# STM32-G0-Dip-Module.net
KiCad netlist of a schematic drawn in EAGLE
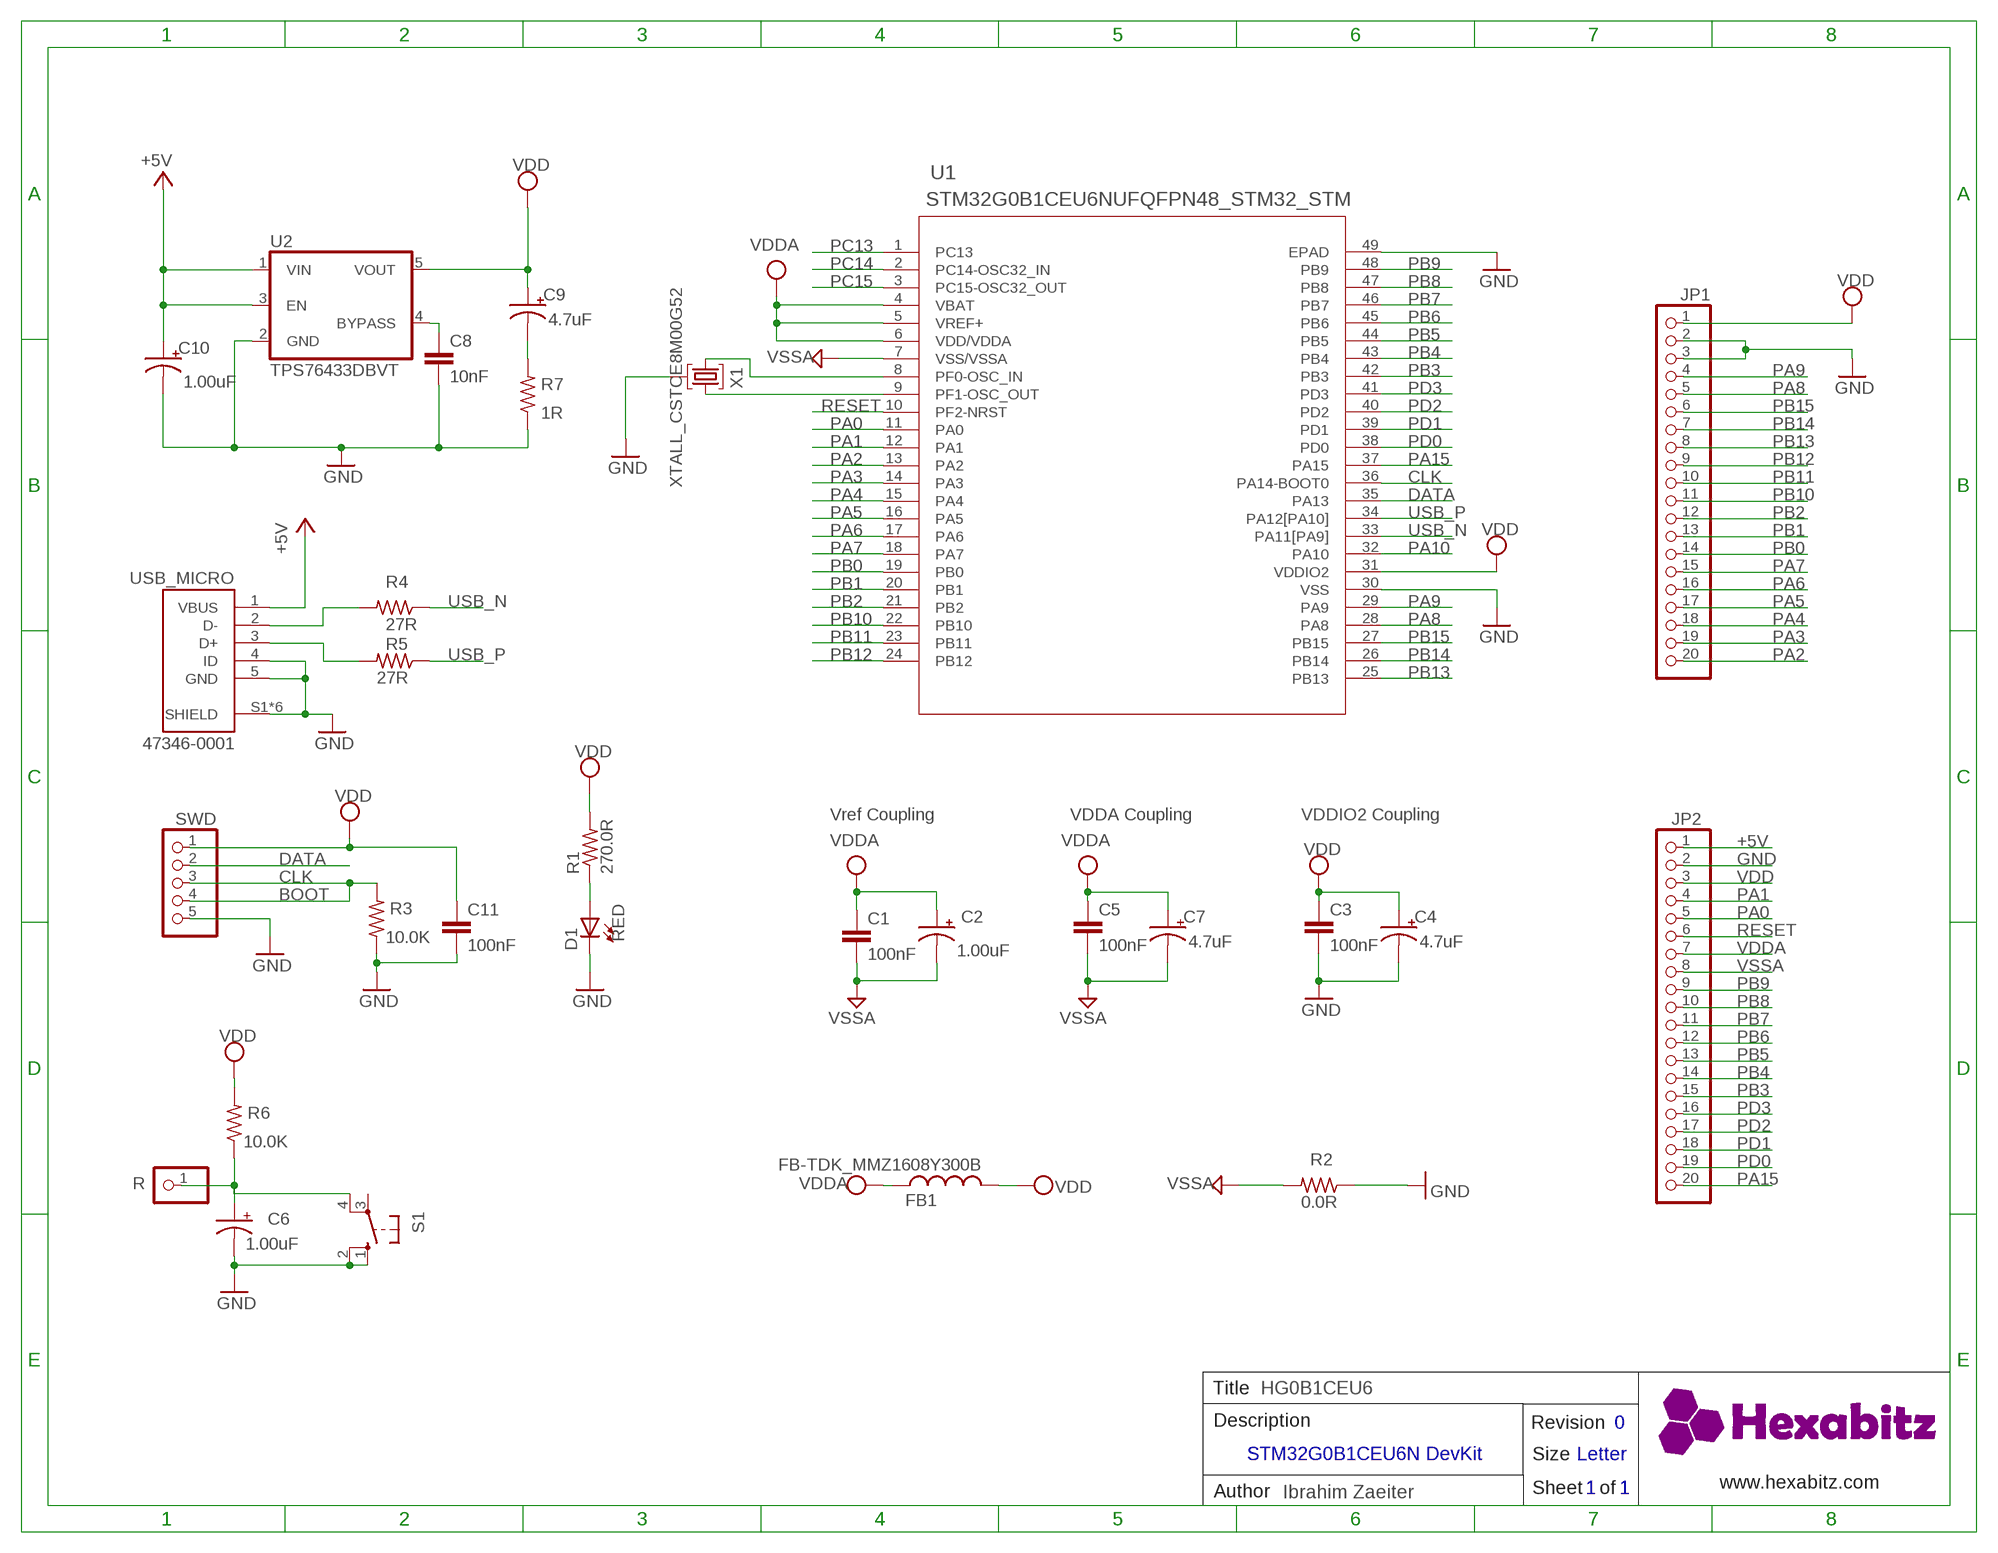
[diagram p0: schematic, sheet 1]

(export (version "E")
  (design (tool "Eeschema 10.0.6"))
  (components
    (comp (ref "C1")
      (value "100nF")
      (footprint "eagle-import:C-0603")
      (fields
        (field (name "CAPACITANCE") "100nF")
        (field (name "MFN") "KEMET")
        (field (name "MPN") "C0603C104K8RACTU")
        (field (name "OCTOPART_URL") "https://octopart.com/c0603c104k8ractu-kemet-145075?r=sp&s=9bS9ASSwSEqMCE9KBEQZ0g")
        (field (name "TOLERANCE") "10%")
        (field (name "VOLTAGE_RATING") "10V")
      )
      (libsource (lib "eagle-import") (part "C-0603"))
    )
    (comp (ref "C2")
      (value "1.00uF")
      (footprint "eagle-import:C-0805-POL")
      (fields
        (field (name "CAPACITANCE") "1.00uF")
        (field (name "MFN") "Yageo")
        (field (name "MPN") "CC0805KKX7R7BB105")
        (field (name "OCTOPART_URL") "https://octopart.com/cc0805kkx7r7bb105-yageo-8376555?r=sp&s=YKl1wwtkROau_X5nniH2ig")
        (field (name "TOLERANCE") "10%")
        (field (name "VOLTAGE_RATING") "16V")
      )
      (libsource (lib "eagle-import") (part "C-0805-POL"))
    )
    (comp (ref "C3")
      (value "100nF")
      (footprint "eagle-import:C-0603")
      (fields
        (field (name "CAPACITANCE") "100nF")
        (field (name "MFN") "KEMET")
        (field (name "MPN") "C0603C104K8RACTU")
        (field (name "OCTOPART_URL") "https://octopart.com/c0603c104k8ractu-kemet-145075?r=sp&s=9bS9ASSwSEqMCE9KBEQZ0g")
        (field (name "TOLERANCE") "10%")
        (field (name "VOLTAGE_RATING") "10V")
      )
      (libsource (lib "eagle-import") (part "C-0603"))
    )
    (comp (ref "C4")
      (value "4.7uF")
      (footprint "eagle-import:C-0805-POL")
      (fields
        (field (name "CAPACITANCE") "4.7uF")
        (field (name "MFN") "Murata")
        (field (name "MPN") "GRM21BC81E475KA12L")
        (field (name "OCTOPART_URL") "https://octopart.com/grm21bc81e475ka12l-murata-10331911?r=sp&s=RY3qZSD8T6mG6TC9CHI5qQ")
        (field (name "TOLERANCE") "10%")
        (field (name "VOLTAGE_RATING") "25V")
      )
      (libsource (lib "eagle-import") (part "C-0805-POL"))
    )
    (comp (ref "C5")
      (value "100nF")
      (footprint "eagle-import:C-0603")
      (fields
        (field (name "CAPACITANCE") "100nF")
        (field (name "MFN") "KEMET")
        (field (name "MPN") "C0603C104K8RACTU")
        (field (name "OCTOPART_URL") "https://octopart.com/c0603c104k8ractu-kemet-145075?r=sp&s=9bS9ASSwSEqMCE9KBEQZ0g")
        (field (name "TOLERANCE") "10%")
        (field (name "VOLTAGE_RATING") "10")
      )
      (libsource (lib "eagle-import") (part "C-0603"))
    )
    (comp (ref "C6")
      (value "1.00uF")
      (footprint "eagle-import:C-0805-POL")
      (fields
        (field (name "CAPACITANCE") "1.00uF")
        (field (name "MFN") "Yageo")
        (field (name "MPN") "CC0805KKX7R7BB105")
        (field (name "OCTOPART_URL") "https://octopart.com/cc0805kkx7r7bb105-yageo-8376555?r=sp&s=YKl1wwtkROau_X5nniH2ig")
        (field (name "TOLERANCE") "10%")
        (field (name "VOLTAGE_RATING") "16V")
      )
      (libsource (lib "eagle-import") (part "C-0805-POL"))
    )
    (comp (ref "C7")
      (value "4.7uF")
      (footprint "eagle-import:C-0805-POL")
      (fields
        (field (name "CAPACITANCE") "4.7uF")
        (field (name "MFN") "Murata")
        (field (name "MPN") "GRM21BC81E475KA12L")
        (field (name "OCTOPART_URL") "https://octopart.com/grm21bc81e475ka12l-murata-10331911?r=sp&s=RY3qZSD8T6mG6TC9CHI5qQ")
        (field (name "TOLERANCE") "10%")
        (field (name "VOLTAGE_RATING") "25V")
      )
      (libsource (lib "eagle-import") (part "C-0805-POL"))
    )
    (comp (ref "C8")
      (value "10nF")
      (footprint "eagle-import:C-0603")
      (fields
        (field (name "CAPACITANCE") "100nF")
        (field (name "MFN") "KEMET")
        (field (name "MPN") "C0603C104K8RACTU")
        (field (name "OCTOPART_URL") "https://octopart.com/c0603c104k8ractu-kemet-145075?r=sp&s=9bS9ASSwSEqMCE9KBEQZ0g")
        (field (name "TOLERANCE") "10%")
        (field (name "VOLTAGE_RATING") "10")
      )
      (libsource (lib "eagle-import") (part "C-0603"))
    )
    (comp (ref "C9")
      (value "4.7uF")
      (footprint "eagle-import:C-0805-POL")
      (fields
        (field (name "CAPACITANCE") "4.7uF")
        (field (name "MFN") "Murata")
        (field (name "MPN") "GRM21BC81E475KA12L")
        (field (name "OCTOPART_URL") "https://octopart.com/grm21bc81e475ka12l-murata-10331911?r=sp&s=RY3qZSD8T6mG6TC9CHI5qQ")
        (field (name "TOLERANCE") "10%")
        (field (name "VOLTAGE_RATING") "25V")
      )
      (libsource (lib "eagle-import") (part "C-0805-POL"))
    )
    (comp (ref "C10")
      (value "1.00uF")
      (footprint "eagle-import:C-0805-POL")
      (fields
        (field (name "CAPACITANCE") "1.00uF")
        (field (name "MFN") "Yageo")
        (field (name "MPN") "CC0805KKX7R7BB105")
        (field (name "OCTOPART_URL") "https://octopart.com/cc0805kkx7r7bb105-yageo-8376555?r=sp&s=YKl1wwtkROau_X5nniH2ig")
        (field (name "TOLERANCE") "10%")
        (field (name "VOLTAGE_RATING") "16V")
      )
      (libsource (lib "eagle-import") (part "C-0805-POL"))
    )
    (comp (ref "C11")
      (value "100nF")
      (footprint "eagle-import:C-0603")
      (fields
        (field (name "CAPACITANCE") "100nF")
        (field (name "MFN") "KEMET")
        (field (name "MPN") "C0603C104K8RACTU")
        (field (name "OCTOPART_URL") "https://octopart.com/c0603c104k8ractu-kemet-145075?r=sp&s=9bS9ASSwSEqMCE9KBEQZ0g")
        (field (name "TOLERANCE") "10%")
        (field (name "VOLTAGE_RATING") "10V")
      )
      (libsource (lib "eagle-import") (part "C-0603"))
    )
    (comp (ref "D1")
      (value "RED")
      (footprint "eagle-import:VLMS1300-GS08")
      (fields
        (field (name "MPN") "VLMS1300-GS08")
        (field (name "MFN") "Vishay")
        (field (name "MPN_1") "VLMS1300-GS08")
        (field (name "OCTOPART_URL") "https://octopart.com/vlms1300-gs08-vishay-21709201?r=sp&s=_gcP4_q8T1SC6PJQPTQ9yA")
      )
      (libsource (lib "eagle-import") (part "VLMS1300-GS08"))
    )
    (comp (ref "FB1")
      (value "FB-TDK_MMZ1608Y300B")
      (footprint "eagle-import:FB-TDK_MMZ1608Y300B")
      (fields
        (field (name "MFN") "TDK ")
        (field (name "MPN") "MMZ1608Y300B")
        (field (name "OCTOPART_URL") "https://octopart.com/mmz1608y300b-tdk-368280?r=sp&s=cd9_2ZEqQ9q9UNBuQgHAiA")
      )
      (libsource (lib "eagle-import") (part "FB-TDK_MMZ1608Y300B"))
    )
    (comp (ref "JP1")
      (value "PINHD-1X20")
      (footprint "eagle-import:1X20")
      (libsource (lib "eagle-import") (part "PINHD-1X20"))
    )
    (comp (ref "JP2")
      (value "PINHD-1X20")
      (footprint "eagle-import:1X20")
      (libsource (lib "eagle-import") (part "PINHD-1X20"))
    )
    (comp (ref "R")
      (value "PINHD-1X1")
      (footprint "eagle-import:1X01")
      (fields (field (name "MPN") "87227-1"))
      (libsource (lib "eagle-import") (part "PINHD-1X1"))
    )
    (comp (ref "R1")
      (value "270.0R")
      (footprint "eagle-import:R-0603")
      (fields
        (field (name "MFN") "Yageo")
        (field (name "MPN") "RC0603FR-07270RL")
        (field (name "OCTOPART_URL") "https://octopart.com/search?q=RC0603FR-07270RL&start=0")
        (field (name "RESISTANCE") "270.0 Ohm")
        (field (name "TOLERANCE") "1%")
      )
      (libsource (lib "eagle-import") (part "R-0603"))
    )
    (comp (ref "R2")
      (value "0.0R")
      (footprint "eagle-import:R-0603")
      (fields
        (field (name "MFN") "Yageo")
        (field (name "MPN") "RC0603JR-070RL")
        (field (name "OCTOPART_URL") "https://octopart.com/rc0603jr-070rl-yageo-1241539?r=sp&s=X2NteqRjRNWrnx42Y0aliA")
        (field (name "RESISTANCE") "0.0 Ohm")
      )
      (libsource (lib "eagle-import") (part "R-0603"))
    )
    (comp (ref "R3")
      (value "10.0K")
      (footprint "eagle-import:R-0603")
      (fields
        (field (name "MFN") "Yageo")
        (field (name "MPN") "RC0603JR-0710KL")
        (field (name "OCTOPART_URL") "https://octopart.com/search?q=RC0603JR-0710KL&start=0")
        (field (name "RESISTANCE") "10.0K Ohm")
        (field (name "TOLERANCE") "5%")
      )
      (libsource (lib "eagle-import") (part "R-0603"))
    )
    (comp (ref "R4")
      (value "27R")
      (footprint "eagle-import:R-0603")
      (fields
        (field (name "MFN") "Yageo")
        (field (name "MPN") "RC0603JR-0710KL")
        (field (name "OCTOPART_URL") "https://octopart.com/search?q=RC0603JR-0710KL&start=0")
        (field (name "RESISTANCE") "10.0K Ohm")
        (field (name "TOLERANCE") "5%")
      )
      (libsource (lib "eagle-import") (part "R-0603"))
    )
    (comp (ref "R5")
      (value "27R")
      (footprint "eagle-import:R-0603")
      (fields
        (field (name "MFN") "Yageo")
        (field (name "MPN") "RC0603JR-0710KL")
        (field (name "OCTOPART_URL") "https://octopart.com/search?q=RC0603JR-0710KL&start=0")
        (field (name "RESISTANCE") "10.0K Ohm")
        (field (name "TOLERANCE") "5%")
      )
      (libsource (lib "eagle-import") (part "R-0603"))
    )
    (comp (ref "R6")
      (value "10.0K")
      (footprint "eagle-import:R-0603")
      (fields
        (field (name "MFN") "Yageo")
        (field (name "MPN") "RC0603JR-0710KL")
        (field (name "OCTOPART_URL") "https://octopart.com/search?q=RC0603JR-0710KL&start=0")
        (field (name "RESISTANCE") "10.0K Ohm")
        (field (name "TOLERANCE") "5%")
      )
      (libsource (lib "eagle-import") (part "R-0603"))
    )
    (comp (ref "R7")
      (value "1R")
      (footprint "eagle-import:R-0603")
      (fields
        (field (name "MFN") "Yageo")
        (field (name "MPN") "RC0603JR-0710KL")
        (field (name "OCTOPART_URL") "https://octopart.com/search?q=RC0603JR-0710KL&start=0")
        (field (name "RESISTANCE") "10.0K Ohm")
        (field (name "TOLERANCE") "5%")
      )
      (libsource (lib "eagle-import") (part "R-0603"))
    )
    (comp (ref "S1")
      (value "10-XX")
      (footprint "eagle-import:B3F-10XX")
      (fields (field (name "MPN") "B3F-1000"))
      (libsource (lib "eagle-import") (part "10-XX"))
    )
    (comp (ref "SWD")
      (value "PINHD-1X5/90")
      (footprint "eagle-import:1X05_90")
      (libsource (lib "eagle-import") (part "PINHD-1X5/90"))
    )
    (comp (ref "U1")
      (value "STM32G0B1CEU6NUFQFPN48_STM32_STM")
      (footprint "eagle-import:UFQFPN48_STM32_STM")
      (fields
        (field (name "MPN") "STM32G0B1CEU6N")
        (field (name "COPYRIGHT") "Copyright (C) 2022 Ultra Librarian. All rights reserved.")
      )
      (libsource (lib "eagle-import") (part "STM32G0B1CEU6NUFQFPN48_STM32_STM"))
    )
    (comp (ref "U2")
      (value "TPS76433DBVT")
      (footprint "eagle-import:SOT25")
      (libsource (lib "eagle-import") (part "TPS764DBVT33"))
    )
    (comp (ref "USB_MICRO")
      (value "47346-0001")
      (footprint "eagle-import:MOLEX_47346-0001")
      (fields (field (name "MF") "Molex"))
      (libsource (lib "eagle-import") (part "47346-0001"))
    )
    (comp (ref "X1")
      (value "XTALL_CSTCE8M00G52")
      (footprint "eagle-import:XTALL_CSTCE8M00G52")
      (fields (field (name "MPN") "CSTCE8M00G52Z-R0"))
      (libsource (lib "eagle-import") (part "XTALL_CSTCE8M00G52"))
    )
  )
  (nets
    (net (code "1") (name "+5V") (class "Default")
      (node (ref "C10") (pin "1") (pinfunction "+_1") (pintype "passive"))
      (node (ref "JP2") (pin "1") (pinfunction "1_1") (pintype "passive"))
      (node (ref "U2") (pin "1") (pinfunction "VIN_1") (pintype "input"))
      (node (ref "U2") (pin "3") (pinfunction "EN_3") (pintype "input"))
      (node (ref "USB_MICRO") (pin "1") (pinfunction "VBUS_1") (pintype "power_in"))
    )
    (net (code "2") (name "/CLK") (class "Default")
      (node (ref "R3") (pin "2") (pinfunction "2_2") (pintype "passive"))
      (node (ref "SWD") (pin "3") (pinfunction "3_3") (pintype "passive"))
      (node (ref "SWD") (pin "4") (pinfunction "4_4") (pintype "passive"))
      (node (ref "U1") (pin "36") (pinfunction "PA14-BOOT0_36") (pintype "bidirectional"))
    )
    (net (code "3") (name "/DATA") (class "Default")
      (node (ref "SWD") (pin "2") (pinfunction "2_2") (pintype "passive"))
      (node (ref "U1") (pin "35") (pinfunction "PA13_35") (pintype "bidirectional"))
    )
    (net (code "4") (name "/PA0") (class "Default")
      (node (ref "JP2") (pin "5") (pinfunction "5_5") (pintype "passive"))
      (node (ref "U1") (pin "11") (pinfunction "PA0_11") (pintype "bidirectional"))
    )
    (net (code "5") (name "/PA1") (class "Default")
      (node (ref "JP2") (pin "4") (pinfunction "4_4") (pintype "passive"))
      (node (ref "U1") (pin "12") (pinfunction "PA1_12") (pintype "bidirectional"))
    )
    (net (code "6") (name "/PA2") (class "Default")
      (node (ref "JP1") (pin "20") (pinfunction "20_20") (pintype "passive"))
      (node (ref "U1") (pin "13") (pinfunction "PA2_13") (pintype "bidirectional"))
    )
    (net (code "7") (name "/PA3") (class "Default")
      (node (ref "JP1") (pin "19") (pinfunction "19_19") (pintype "passive"))
      (node (ref "U1") (pin "14") (pinfunction "PA3_14") (pintype "bidirectional"))
    )
    (net (code "8") (name "/PA4") (class "Default")
      (node (ref "JP1") (pin "18") (pinfunction "18_18") (pintype "passive"))
      (node (ref "U1") (pin "15") (pinfunction "PA4_15") (pintype "bidirectional"))
    )
    (net (code "9") (name "/PA5") (class "Default")
      (node (ref "JP1") (pin "17") (pinfunction "17_17") (pintype "passive"))
      (node (ref "U1") (pin "16") (pinfunction "PA5_16") (pintype "bidirectional"))
    )
    (net (code "10") (name "/PA6") (class "Default")
      (node (ref "JP1") (pin "16") (pinfunction "16_16") (pintype "passive"))
      (node (ref "U1") (pin "17") (pinfunction "PA6_17") (pintype "bidirectional"))
    )
    (net (code "11") (name "/PA7") (class "Default")
      (node (ref "JP1") (pin "15") (pinfunction "15_15") (pintype "passive"))
      (node (ref "U1") (pin "18") (pinfunction "PA7_18") (pintype "bidirectional"))
    )
    (net (code "12") (name "/PA8") (class "Default")
      (node (ref "JP1") (pin "5") (pinfunction "5_5") (pintype "passive"))
      (node (ref "U1") (pin "28") (pinfunction "PA8_28") (pintype "bidirectional"))
    )
    (net (code "13") (name "/PA9") (class "Default")
      (node (ref "JP1") (pin "4") (pinfunction "4_4") (pintype "passive"))
      (node (ref "U1") (pin "29") (pinfunction "PA9_29") (pintype "bidirectional"))
    )
    (net (code "14") (name "/PA10") (class "Default")
      (node (ref "U1") (pin "32") (pinfunction "PA10_32") (pintype "bidirectional"))
    )
    (net (code "15") (name "/PA15") (class "Default")
      (node (ref "JP2") (pin "20") (pinfunction "20_20") (pintype "passive"))
      (node (ref "U1") (pin "37") (pinfunction "PA15_37") (pintype "bidirectional"))
    )
    (net (code "16") (name "/PB0") (class "Default")
      (node (ref "JP1") (pin "14") (pinfunction "14_14") (pintype "passive"))
      (node (ref "U1") (pin "19") (pinfunction "PB0_19") (pintype "bidirectional"))
    )
    (net (code "17") (name "/PB1") (class "Default")
      (node (ref "JP1") (pin "13") (pinfunction "13_13") (pintype "passive"))
      (node (ref "U1") (pin "20") (pinfunction "PB1_20") (pintype "bidirectional"))
    )
    (net (code "18") (name "/PB2") (class "Default")
      (node (ref "JP1") (pin "12") (pinfunction "12_12") (pintype "passive"))
      (node (ref "U1") (pin "21") (pinfunction "PB2_21") (pintype "bidirectional"))
    )
    (net (code "19") (name "/PB3") (class "Default")
      (node (ref "JP2") (pin "15") (pinfunction "15_15") (pintype "passive"))
      (node (ref "U1") (pin "42") (pinfunction "PB3_42") (pintype "bidirectional"))
    )
    (net (code "20") (name "/PB4") (class "Default")
      (node (ref "JP2") (pin "14") (pinfunction "14_14") (pintype "passive"))
      (node (ref "U1") (pin "43") (pinfunction "PB4_43") (pintype "bidirectional"))
    )
    (net (code "21") (name "/PB5") (class "Default")
      (node (ref "JP2") (pin "13") (pinfunction "13_13") (pintype "passive"))
      (node (ref "U1") (pin "44") (pinfunction "PB5_44") (pintype "bidirectional"))
    )
    (net (code "22") (name "/PB6") (class "Default")
      (node (ref "JP2") (pin "12") (pinfunction "12_12") (pintype "passive"))
      (node (ref "U1") (pin "45") (pinfunction "PB6_45") (pintype "bidirectional"))
    )
    (net (code "23") (name "/PB7") (class "Default")
      (node (ref "JP2") (pin "11") (pinfunction "11_11") (pintype "passive"))
      (node (ref "U1") (pin "46") (pinfunction "PB7_46") (pintype "bidirectional"))
    )
    (net (code "24") (name "/PB8") (class "Default")
      (node (ref "JP2") (pin "10") (pinfunction "10_10") (pintype "passive"))
      (node (ref "U1") (pin "47") (pinfunction "PB8_47") (pintype "bidirectional"))
    )
    (net (code "25") (name "/PB9") (class "Default")
      (node (ref "JP2") (pin "9") (pinfunction "9_9") (pintype "passive"))
      (node (ref "U1") (pin "48") (pinfunction "PB9_48") (pintype "bidirectional"))
    )
    (net (code "26") (name "/PB10") (class "Default")
      (node (ref "JP1") (pin "11") (pinfunction "11_11") (pintype "passive"))
      (node (ref "U1") (pin "22") (pinfunction "PB10_22") (pintype "bidirectional"))
    )
    (net (code "27") (name "/PB11") (class "Default")
      (node (ref "JP1") (pin "10") (pinfunction "10_10") (pintype "passive"))
      (node (ref "U1") (pin "23") (pinfunction "PB11_23") (pintype "bidirectional"))
    )
    (net (code "28") (name "/PB12") (class "Default")
      (node (ref "JP1") (pin "9") (pinfunction "9_9") (pintype "passive"))
      (node (ref "U1") (pin "24") (pinfunction "PB12_24") (pintype "bidirectional"))
    )
    (net (code "29") (name "/PB13") (class "Default")
      (node (ref "JP1") (pin "8") (pinfunction "8_8") (pintype "passive"))
      (node (ref "U1") (pin "25") (pinfunction "PB13_25") (pintype "bidirectional"))
    )
    (net (code "30") (name "/PB14") (class "Default")
      (node (ref "JP1") (pin "7") (pinfunction "7_7") (pintype "passive"))
      (node (ref "U1") (pin "26") (pinfunction "PB14_26") (pintype "bidirectional"))
    )
    (net (code "31") (name "/PB15") (class "Default")
      (node (ref "JP1") (pin "6") (pinfunction "6_6") (pintype "passive"))
      (node (ref "U1") (pin "27") (pinfunction "PB15_27") (pintype "bidirectional"))
    )
    (net (code "32") (name "/PC13") (class "Default")
      (node (ref "U1") (pin "1") (pinfunction "PC13_1") (pintype "bidirectional"))
    )
    (net (code "33") (name "/PC14") (class "Default")
      (node (ref "U1") (pin "2") (pinfunction "PC14-OSC32_IN_2") (pintype "bidirectional"))
    )
    (net (code "34") (name "/PC15") (class "Default")
      (node (ref "U1") (pin "3") (pinfunction "PC15-OSC32_OUT_3") (pintype "bidirectional"))
    )
    (net (code "35") (name "/PD0") (class "Default")
      (node (ref "JP2") (pin "19") (pinfunction "19_19") (pintype "passive"))
      (node (ref "U1") (pin "38") (pinfunction "PD0_38") (pintype "bidirectional"))
    )
    (net (code "36") (name "/PD1") (class "Default")
      (node (ref "JP2") (pin "18") (pinfunction "18_18") (pintype "passive"))
      (node (ref "U1") (pin "39") (pinfunction "PD1_39") (pintype "bidirectional"))
    )
    (net (code "37") (name "/PD2") (class "Default")
      (node (ref "JP2") (pin "17") (pinfunction "17_17") (pintype "passive"))
      (node (ref "U1") (pin "40") (pinfunction "PD2_40") (pintype "bidirectional"))
    )
    (net (code "38") (name "/PD3") (class "Default")
      (node (ref "JP2") (pin "16") (pinfunction "16_16") (pintype "passive"))
      (node (ref "U1") (pin "41") (pinfunction "PD3_41") (pintype "bidirectional"))
    )
    (net (code "39") (name "/RESET") (class "Default")
      (node (ref "C6") (pin "1") (pinfunction "+_1") (pintype "passive"))
      (node (ref "JP2") (pin "6") (pinfunction "6_6") (pintype "passive"))
      (node (ref "R") (pin "1") (pinfunction "1_1") (pintype "passive"))
      (node (ref "R6") (pin "1") (pinfunction "1_1") (pintype "passive"))
      (node (ref "S1") (pin "4") (pinfunction "P1_4") (pintype "passive"))
      (node (ref "U1") (pin "10") (pinfunction "PF2-NRST_10") (pintype "bidirectional"))
    )
    (net (code "40") (name "/USB_N") (class "Default")
      (node (ref "R4") (pin "1") (pinfunction "1_1") (pintype "passive"))
      (node (ref "U1") (pin "33") (pinfunction "PA11[PA9]_33") (pintype "bidirectional"))
    )
    (net (code "41") (name "/USB_P") (class "Default")
      (node (ref "R5") (pin "1") (pinfunction "1_1") (pintype "passive"))
      (node (ref "U1") (pin "34") (pinfunction "PA12[PA10]_34") (pintype "bidirectional"))
    )
    (net (code "42") (name "GND") (class "Default")
      (node (ref "C10") (pin "2") (pinfunction "-_2") (pintype "passive"))
      (node (ref "C11") (pin "2") (pinfunction "2_2") (pintype "passive"))
      (node (ref "C3") (pin "2") (pinfunction "2_2") (pintype "passive"))
      (node (ref "C4") (pin "2") (pinfunction "-_2") (pintype "passive"))
      (node (ref "C6") (pin "2") (pinfunction "-_2") (pintype "passive"))
      (node (ref "C8") (pin "2") (pinfunction "2_2") (pintype "passive"))
      (node (ref "D1") (pin "C") (pinfunction "C_C") (pintype "passive"))
      (node (ref "JP1") (pin "2") (pinfunction "2_2") (pintype "passive"))
      (node (ref "JP1") (pin "3") (pinfunction "3_3") (pintype "passive"))
      (node (ref "JP2") (pin "2") (pinfunction "2_2") (pintype "passive"))
      (node (ref "R2") (pin "1") (pinfunction "1_1") (pintype "passive"))
      (node (ref "R3") (pin "1") (pinfunction "1_1") (pintype "passive"))
      (node (ref "R7") (pin "1") (pinfunction "1_1") (pintype "passive"))
      (node (ref "S1") (pin "1") (pinfunction "S_1") (pintype "passive"))
      (node (ref "S1") (pin "2") (pinfunction "S1_2") (pintype "passive"))
      (node (ref "SWD") (pin "5") (pinfunction "5_5") (pintype "passive"))
      (node (ref "U1") (pin "30") (pinfunction "VSS_30") (pintype "passive"))
      (node (ref "U1") (pin "49") (pinfunction "EPAD_49") (pintype "passive"))
      (node (ref "U2") (pin "2") (pinfunction "GND_2") (pintype "passive"))
      (node (ref "USB_MICRO") (pin "4") (pinfunction "ID_4") (pintype "bidirectional"))
      (node (ref "USB_MICRO") (pin "5") (pinfunction "GND_5") (pintype "power_in"))
      (node (ref "USB_MICRO") (pin "S1") (pinfunction "SHIELD_S1") (pintype "passive"))
      (node (ref "USB_MICRO") (pin "S2") (pinfunction "SHIELD_S2") (pintype "passive"))
      (node (ref "USB_MICRO") (pin "S3") (pinfunction "SHIELD_S3") (pintype "passive"))
      (node (ref "USB_MICRO") (pin "S4") (pinfunction "SHIELD_S4") (pintype "passive"))
      (node (ref "USB_MICRO") (pin "S5") (pinfunction "SHIELD_S5") (pintype "passive"))
      (node (ref "USB_MICRO") (pin "S6") (pinfunction "SHIELD_S6") (pintype "passive"))
      (node (ref "X1") (pin "P$2") (pinfunction "2_P$2") (pintype "passive"))
    )
    (net (code "43") (name "Net-(C9--)") (class "Default")
      (node (ref "C9") (pin "2") (pinfunction "-_2") (pintype "passive"))
      (node (ref "R7") (pin "2") (pinfunction "2_2") (pintype "passive"))
    )
    (net (code "44") (name "Net-(D1-PadA)") (class "Default")
      (node (ref "D1") (pin "A") (pinfunction "A_A") (pintype "passive"))
      (node (ref "R1") (pin "1") (pinfunction "1_1") (pintype "passive"))
    )
    (net (code "45") (name "Net-(U1-PF0-OSC_IN)") (class "Default")
      (node (ref "U1") (pin "8") (pinfunction "PF0-OSC_IN_8") (pintype "bidirectional"))
      (node (ref "X1") (pin "P$1") (pinfunction "1_P$1") (pintype "passive"))
    )
    (net (code "46") (name "Net-(U1-PF1-OSC_OUT)") (class "Default")
      (node (ref "U1") (pin "9") (pinfunction "PF1-OSC_OUT_9") (pintype "bidirectional"))
      (node (ref "X1") (pin "P$3") (pinfunction "3_P$3") (pintype "passive"))
    )
    (net (code "47") (name "Net-(U2-BYPASS)") (class "Default")
      (node (ref "C8") (pin "1") (pinfunction "1_1") (pintype "passive"))
      (node (ref "U2") (pin "4") (pinfunction "BYPASS_4") (pintype "input"))
    )
    (net (code "48") (name "Net-(USB_MICRO-D+)") (class "Default")
      (node (ref "R5") (pin "2") (pinfunction "2_2") (pintype "passive"))
      (node (ref "USB_MICRO") (pin "3") (pinfunction "D+_3") (pintype "bidirectional"))
    )
    (net (code "49") (name "Net-(USB_MICRO-D-)") (class "Default")
      (node (ref "R4") (pin "2") (pinfunction "2_2") (pintype "passive"))
      (node (ref "USB_MICRO") (pin "2") (pinfunction "D-_2") (pintype "bidirectional"))
    )
    (net (code "50") (name "VDD") (class "Default")
      (node (ref "C11") (pin "1") (pinfunction "1_1") (pintype "passive"))
      (node (ref "C3") (pin "1") (pinfunction "1_1") (pintype "passive"))
      (node (ref "C4") (pin "1") (pinfunction "+_1") (pintype "passive"))
      (node (ref "C9") (pin "1") (pinfunction "+_1") (pintype "passive"))
      (node (ref "FB1") (pin "2") (pinfunction "2_2") (pintype "passive"))
      (node (ref "JP1") (pin "1") (pinfunction "1_1") (pintype "passive"))
      (node (ref "JP2") (pin "3") (pinfunction "3_3") (pintype "passive"))
      (node (ref "R1") (pin "2") (pinfunction "2_2") (pintype "passive"))
      (node (ref "R6") (pin "2") (pinfunction "2_2") (pintype "passive"))
      (node (ref "SWD") (pin "1") (pinfunction "1_1") (pintype "passive"))
      (node (ref "U1") (pin "31") (pinfunction "VDDIO2_31") (pintype "power_in"))
      (node (ref "U2") (pin "5") (pinfunction "VOUT_5") (pintype "passive"))
    )
    (net (code "51") (name "VDDA") (class "Default")
      (node (ref "C1") (pin "1") (pinfunction "1_1") (pintype "passive"))
      (node (ref "C2") (pin "1") (pinfunction "+_1") (pintype "passive"))
      (node (ref "C5") (pin "1") (pinfunction "1_1") (pintype "passive"))
      (node (ref "C7") (pin "1") (pinfunction "+_1") (pintype "passive"))
      (node (ref "FB1") (pin "1") (pinfunction "1_1") (pintype "passive"))
      (node (ref "JP2") (pin "7") (pinfunction "7_7") (pintype "passive"))
      (node (ref "U1") (pin "4") (pinfunction "VBAT_4") (pintype "power_in"))
      (node (ref "U1") (pin "5") (pinfunction "VREF+_5") (pintype "power_in"))
      (node (ref "U1") (pin "6") (pinfunction "VDD/VDDA_6") (pintype "power_in"))
    )
    (net (code "52") (name "VSSA") (class "Default")
      (node (ref "C1") (pin "2") (pinfunction "2_2") (pintype "passive"))
      (node (ref "C2") (pin "2") (pinfunction "-_2") (pintype "passive"))
      (node (ref "C5") (pin "2") (pinfunction "2_2") (pintype "passive"))
      (node (ref "C7") (pin "2") (pinfunction "-_2") (pintype "passive"))
      (node (ref "JP2") (pin "8") (pinfunction "8_8") (pintype "passive"))
      (node (ref "R2") (pin "2") (pinfunction "2_2") (pintype "passive"))
      (node (ref "U1") (pin "7") (pinfunction "VSS/VSSA_7") (pintype "passive"))
    )
    (net (code "53") (name "unconnected-(S1-P-Pad3)") (class "Default")
      (node (ref "S1") (pin "3") (pinfunction "P_3") (pintype "passive"))
    )
  )
)
